# Base_XIAO_v7.net
KiCad netlist of a schematic drawn in EAGLE
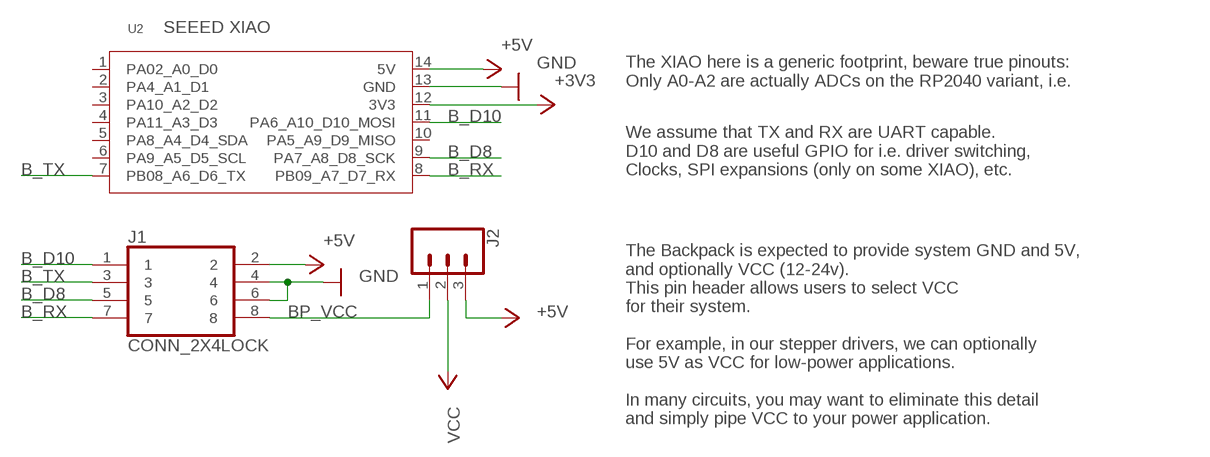
[diagram p0: schematic, sheet 1]

(export (version "E")
  (design (tool "Eeschema 10.0.6"))
  (components
    (comp (ref "J1")
      (value "CONN_2X4LOCK")
      (footprint "eagle-import:2X4-LOCK")
      (libsource (lib "eagle-import") (part "CONN_2X4LOCK"))
    )
    (comp (ref "J2")
      (value "CONN_03LOCK_NO_SILK")
      (footprint "eagle-import:1X03_LOCK_NO_SILK")
      (libsource (lib "eagle-import") (part "CONN_03LOCK_NO_SILK"))
    )
    (comp (ref "U2")
      (value "MOUDLE-SEEEDUINO-XIAO-DIP")
      (footprint "eagle-import:MOUDLE14P-2.54-21X17.8MM")
      (libsource (lib "eagle-import") (part "MOUDLE-SEEEDUINO-XIAO-DIP"))
    )
  )
  (nets
    (net (code "1") (name "+3V3") (class "Default")
      (node (ref "U2") (pin "12") (pinfunction "3V3_12") (pintype "bidirectional"))
    )
    (net (code "2") (name "+5V") (class "Default")
      (node (ref "J1") (pin "2") (pinfunction "2_2") (pintype "passive"))
      (node (ref "J2") (pin "3") (pinfunction "3_3") (pintype "passive"))
      (node (ref "U2") (pin "14") (pinfunction "5V_14") (pintype "bidirectional"))
    )
    (net (code "3") (name "/BP_VCC") (class "Default")
      (node (ref "J1") (pin "8") (pinfunction "8_8") (pintype "passive"))
      (node (ref "J2") (pin "1") (pinfunction "1_1") (pintype "passive"))
    )
    (net (code "4") (name "/B_D8") (class "Default")
      (node (ref "J1") (pin "5") (pinfunction "5_5") (pintype "passive"))
      (node (ref "U2") (pin "9") (pinfunction "PA7_A8_D8_SCK_9") (pintype "bidirectional"))
    )
    (net (code "5") (name "/B_D10") (class "Default")
      (node (ref "J1") (pin "1") (pinfunction "1_1") (pintype "passive"))
      (node (ref "U2") (pin "11") (pinfunction "PA6_A10_D10_MOSI_11") (pintype "bidirectional"))
    )
    (net (code "6") (name "/B_RX") (class "Default")
      (node (ref "J1") (pin "7") (pinfunction "7_7") (pintype "passive"))
      (node (ref "U2") (pin "8") (pinfunction "PB09_A7_D7_RX_8") (pintype "bidirectional"))
    )
    (net (code "7") (name "/B_TX") (class "Default")
      (node (ref "J1") (pin "3") (pinfunction "3_3") (pintype "passive"))
      (node (ref "U2") (pin "7") (pinfunction "PB08_A6_D6_TX_7") (pintype "bidirectional"))
    )
    (net (code "8") (name "GND") (class "Default")
      (node (ref "J1") (pin "4") (pinfunction "4_4") (pintype "passive"))
      (node (ref "J1") (pin "6") (pinfunction "6_6") (pintype "passive"))
      (node (ref "U2") (pin "13") (pinfunction "GND_13") (pintype "bidirectional"))
    )
    (net (code "9") (name "VCC") (class "Default")
      (node (ref "J2") (pin "2") (pinfunction "2_2") (pintype "passive"))
    )
    (net (code "10") (name "unconnected-(U2-PA02_A0_D0-Pad1)") (class "Default")
      (node (ref "U2") (pin "1") (pinfunction "PA02_A0_D0_1") (pintype "bidirectional"))
    )
    (net (code "11") (name "unconnected-(U2-PA4_A1_D1-Pad2)") (class "Default")
      (node (ref "U2") (pin "2") (pinfunction "PA4_A1_D1_2") (pintype "bidirectional"))
    )
    (net (code "12") (name "unconnected-(U2-PA5_A9_D9_MISO-Pad10)") (class "Default")
      (node (ref "U2") (pin "10") (pinfunction "PA5_A9_D9_MISO_10") (pintype "bidirectional"))
    )
    (net (code "13") (name "unconnected-(U2-PA8_A4_D4_SDA-Pad5)") (class "Default")
      (node (ref "U2") (pin "5") (pinfunction "PA8_A4_D4_SDA_5") (pintype "bidirectional"))
    )
    (net (code "14") (name "unconnected-(U2-PA9_A5_D5_SCL-Pad6)") (class "Default")
      (node (ref "U2") (pin "6") (pinfunction "PA9_A5_D5_SCL_6") (pintype "bidirectional"))
    )
    (net (code "15") (name "unconnected-(U2-PA10_A2_D2-Pad3)") (class "Default")
      (node (ref "U2") (pin "3") (pinfunction "PA10_A2_D2_3") (pintype "bidirectional"))
    )
    (net (code "16") (name "unconnected-(U2-PA11_A3_D3-Pad4)") (class "Default")
      (node (ref "U2") (pin "4") (pinfunction "PA11_A3_D3_4") (pintype "bidirectional"))
    )
  )
)
